# G2G-A_Module.net
KiCad netlist of a schematic drawn in Altium Designer
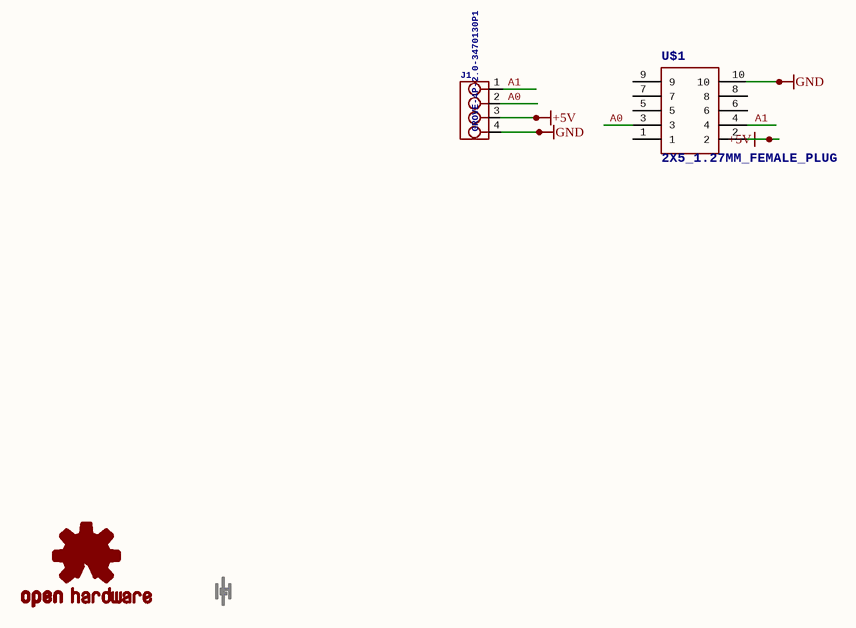
[diagram p0: G2G-A Module.SchDoc]

(export (version "E")
  (design (tool "Eeschema 10.0.6"))
  (components
    (comp (ref "J1")
      (value "GROVE-4P-2.0-3470130P1")
      (footprint "4P-2.0")
      (fields (field (name ">NAME") "J1") (field (name ">VALUE") "GROVE-4P-2.0-3470130P1"))
      (libsource (lib "SoftDust") (part "GROVE-4P-2.0-3470130P1"))
    )
    (comp (ref "LOGO1")
      (value "OSHW-LOGOS")
      (footprint "OSHW-LOGO-S")
      (libsource (lib "SparkFun-Aesthetics") (part "OSHW-LOGOS"))
    )
    (comp (ref "U$1")
      (value "2X5_1.27MM_FEMALE_PLUG")
      (footprint "2X5_1.27MM_FEMALE_PLUG")
      (fields (field (name ">NAME") "U$1") (field (name ">VALUE") "2X5_1.27MM_FEMALE_PLUG"))
      (libsource (lib "SoftDust") (part "2X5_1.27MM_FEMALE_PLUG"))
    )
    (comp (ref "U$2")
      (value "GADGETEER_LOGO_SMALL")
      (footprint "GADGETEER_LOGO_SMALL")
      (libsource (lib "SoftDust") (part "GADGETEER_LOGO_SMALL"))
    )
  )
  (nets
    (net (code "1") (name "+5V") (class "Default")
      (node (ref "J1") (pin "3") (pinfunction "3_3") (pintype "passive"))
      (node (ref "U$1") (pin "2") (pinfunction "2_2") (pintype "passive"))
    )
    (net (code "2") (name "/A0") (class "Default")
      (node (ref "J1") (pin "2") (pinfunction "2_2") (pintype "passive"))
      (node (ref "U$1") (pin "3") (pinfunction "3_3") (pintype "passive"))
    )
    (net (code "3") (name "/A1") (class "Default")
      (node (ref "J1") (pin "1") (pinfunction "1_1") (pintype "passive"))
      (node (ref "U$1") (pin "4") (pinfunction "4_4") (pintype "passive"))
    )
    (net (code "4") (name "GND") (class "Default")
      (node (ref "J1") (pin "4") (pinfunction "4_4") (pintype "passive"))
      (node (ref "U$1") (pin "10") (pinfunction "10_10") (pintype "passive"))
    )
    (net (code "5") (name "unconnected-(U$1-Pad1)") (class "Default")
      (node (ref "U$1") (pin "1") (pinfunction "1_1") (pintype "passive"))
    )
    (net (code "6") (name "unconnected-(U$1-Pad5)") (class "Default")
      (node (ref "U$1") (pin "5") (pinfunction "5_5") (pintype "passive"))
    )
    (net (code "7") (name "unconnected-(U$1-Pad6)") (class "Default")
      (node (ref "U$1") (pin "6") (pinfunction "6_6") (pintype "passive"))
    )
    (net (code "8") (name "unconnected-(U$1-Pad7)") (class "Default")
      (node (ref "U$1") (pin "7") (pinfunction "7_7") (pintype "passive"))
    )
    (net (code "9") (name "unconnected-(U$1-Pad8)") (class "Default")
      (node (ref "U$1") (pin "8") (pinfunction "8_8") (pintype "passive"))
    )
    (net (code "10") (name "unconnected-(U$1-Pad9)") (class "Default")
      (node (ref "U$1") (pin "9") (pinfunction "9_9") (pintype "passive"))
    )
  )
)
